# arduino.net
KiCad netlist of a schematic drawn in EAGLE
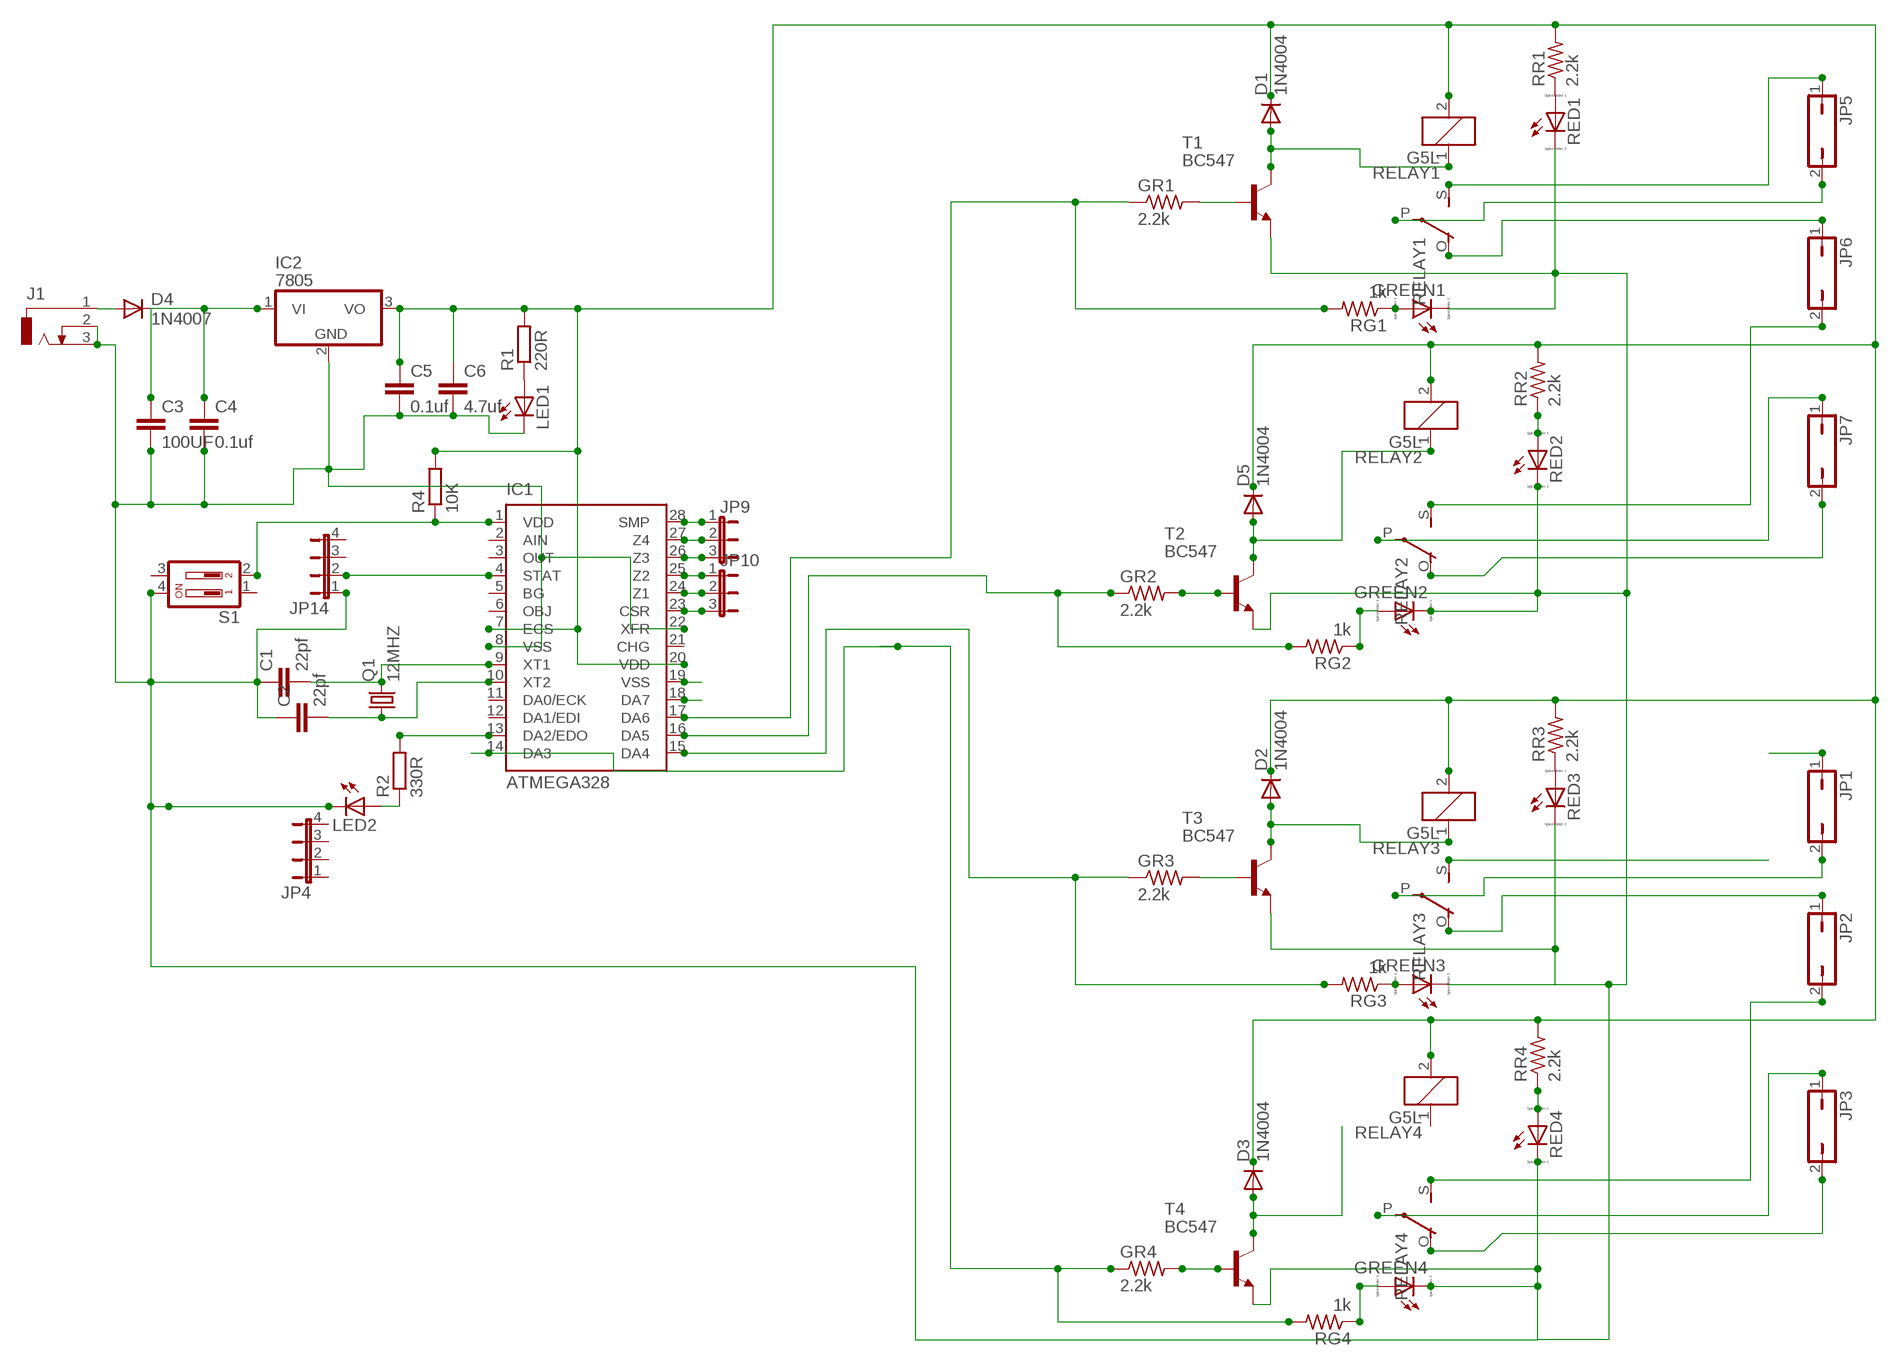
[diagram p0: schematic, sheet 1]

(export (version "E")
  (design (tool "Eeschema 10.0.6"))
  (components
    (comp (ref "C1")
      (value "22pf")
      (footprint "eagle-import:C2.5-2")
      (libsource (lib "eagle-import") (part "C2.5/2"))
    )
    (comp (ref "C2")
      (value "22pf")
      (footprint "eagle-import:C2.5-2")
      (libsource (lib "eagle-import") (part "C2.5/2"))
    )
    (comp (ref "C3")
      (value "100UF")
      (footprint "eagle-import:C2.5-2")
      (libsource (lib "eagle-import") (part "C2.5/2"))
    )
    (comp (ref "C4")
      (value "0.1uf")
      (footprint "eagle-import:C2.5-2")
      (libsource (lib "eagle-import") (part "C2.5/2"))
    )
    (comp (ref "C5")
      (value "0.1uf")
      (footprint "eagle-import:C2.5-2")
      (libsource (lib "eagle-import") (part "C2.5/2"))
    )
    (comp (ref "C6")
      (value "4.7uf")
      (footprint "eagle-import:C2.5-2")
      (libsource (lib "eagle-import") (part "C2.5/2"))
    )
    (comp (ref "D1")
      (value "1N4004")
      (footprint "eagle-import:DO41-10")
      (libsource (lib "eagle-import") (part "1N4004"))
    )
    (comp (ref "D2")
      (value "1N4004")
      (footprint "eagle-import:DO41-10")
      (libsource (lib "eagle-import") (part "1N4004"))
    )
    (comp (ref "D3")
      (value "1N4004")
      (footprint "eagle-import:DO41-10")
      (libsource (lib "eagle-import") (part "1N4004"))
    )
    (comp (ref "D4")
      (value "1N4007")
      (footprint "eagle-import:DO41-10")
      (libsource (lib "eagle-import") (part "1N4004"))
    )
    (comp (ref "D5")
      (value "1N4004")
      (footprint "eagle-import:DO41-10")
      (libsource (lib "eagle-import") (part "1N4004"))
    )
    (comp (ref "GR1")
      (value "2.2k")
      (footprint "eagle-import:0204_7")
      (libsource (lib "eagle-import") (part "R-US_0204/7"))
    )
    (comp (ref "GR2")
      (value "2.2k")
      (footprint "eagle-import:0204_7")
      (libsource (lib "eagle-import") (part "R-US_0204/7"))
    )
    (comp (ref "GR3")
      (value "2.2k")
      (footprint "eagle-import:0204_7")
      (libsource (lib "eagle-import") (part "R-US_0204/7"))
    )
    (comp (ref "GR4")
      (value "2.2k")
      (footprint "eagle-import:0204_7")
      (libsource (lib "eagle-import") (part "R-US_0204/7"))
    )
    (comp (ref "GREEN1")
      (value "LED_ELD260")
      (footprint "eagle-import:LED_LD260")
      (libsource (lib "eagle-import") (part "LED_ELD260"))
    )
    (comp (ref "GREEN2")
      (value "LED_ELD260")
      (footprint "eagle-import:LED_LD260")
      (libsource (lib "eagle-import") (part "LED_ELD260"))
    )
    (comp (ref "GREEN3")
      (value "LED_ELD260")
      (footprint "eagle-import:LED_LD260")
      (libsource (lib "eagle-import") (part "LED_ELD260"))
    )
    (comp (ref "GREEN4")
      (value "LED_ELD260")
      (footprint "eagle-import:LED_LD260")
      (libsource (lib "eagle-import") (part "LED_ELD260"))
    )
    (comp (ref "IC1")
      (value "ATMEGA328")
      (footprint "eagle-import:DIL28-3")
      (libsource (lib "eagle-import") (part "QT9701BD"))
    )
    (comp (ref "IC2")
      (value "7805")
      (footprint "eagle-import:TO220V")
      (libsource (lib "eagle-import") (part "78TV6"))
    )
    (comp (ref "J1")
      (value "DCJ0303")
      (footprint "eagle-import:DCJ0303")
      (libsource (lib "eagle-import") (part "DCJ0303"))
    )
    (comp (ref "JP1")
      (value "JP1Q")
      (footprint "eagle-import:JP1")
      (libsource (lib "eagle-import") (part "JP1Q"))
    )
    (comp (ref "JP2")
      (value "JP1Q")
      (footprint "eagle-import:JP1")
      (libsource (lib "eagle-import") (part "JP1Q"))
    )
    (comp (ref "JP3")
      (value "JP1Q")
      (footprint "eagle-import:JP1")
      (libsource (lib "eagle-import") (part "JP1Q"))
    )
    (comp (ref "JP4")
      (value "JP4E")
      (footprint "eagle-import:JP4")
      (libsource (lib "eagle-import") (part "JP4E"))
    )
    (comp (ref "JP5")
      (value "JP1Q")
      (footprint "eagle-import:JP1")
      (libsource (lib "eagle-import") (part "JP1Q"))
    )
    (comp (ref "JP6")
      (value "JP1Q")
      (footprint "eagle-import:JP1")
      (libsource (lib "eagle-import") (part "JP1Q"))
    )
    (comp (ref "JP7")
      (value "JP1Q")
      (footprint "eagle-import:JP1")
      (libsource (lib "eagle-import") (part "JP1Q"))
    )
    (comp (ref "JP9")
      (value "JP2E")
      (footprint "eagle-import:JP2")
      (libsource (lib "eagle-import") (part "JP2E"))
    )
    (comp (ref "JP10")
      (value "JP2E")
      (footprint "eagle-import:JP2")
      (libsource (lib "eagle-import") (part "JP2E"))
    )
    (comp (ref "JP14")
      (value "JP4E")
      (footprint "eagle-import:JP4")
      (libsource (lib "eagle-import") (part "JP4E"))
    )
    (comp (ref "LED1")
      (value "LED3MM")
      (footprint "eagle-import:LED3MM")
      (libsource (lib "eagle-import") (part "LED3MM"))
    )
    (comp (ref "LED2")
      (value "LED3MM")
      (footprint "eagle-import:LED3MM")
      (libsource (lib "eagle-import") (part "LED3MM"))
    )
    (comp (ref "Q1")
      (value "12MHZ")
      (footprint "eagle-import:HC49_S")
      (libsource (lib "eagle-import") (part "CRYSTALHC49S"))
    )
    (comp (ref "R1")
      (value "220R")
      (footprint "eagle-import:0207_10")
      (libsource (lib "eagle-import") (part "R-EU_0207/10"))
    )
    (comp (ref "R2")
      (value "330R")
      (footprint "eagle-import:0207_10")
      (libsource (lib "eagle-import") (part "R-EU_0207/10"))
    )
    (comp (ref "R4")
      (value "10K")
      (footprint "eagle-import:0207_10")
      (libsource (lib "eagle-import") (part "R-EU_0207/10"))
    )
    (comp (ref "RED1")
      (value "LED_ELD260")
      (footprint "eagle-import:LED_LD260")
      (libsource (lib "eagle-import") (part "LED_ELD260"))
    )
    (comp (ref "RED2")
      (value "LED_ELD260")
      (footprint "eagle-import:LED_LD260")
      (libsource (lib "eagle-import") (part "LED_ELD260"))
    )
    (comp (ref "RED3")
      (value "LED_ELD260")
      (footprint "eagle-import:LED_LD260")
      (libsource (lib "eagle-import") (part "LED_ELD260"))
    )
    (comp (ref "RED4")
      (value "LED_ELD260")
      (footprint "eagle-import:LED_LD260")
      (libsource (lib "eagle-import") (part "LED_ELD260"))
    )
    (comp (ref "RELAY1")
      (value "G5L")
      (footprint "eagle-import:G5LE")
      (libsource (lib "eagle-import") (part "G5L"))
    )
    (comp (ref "RELAY2")
      (value "G5L")
      (footprint "eagle-import:G5LE")
      (libsource (lib "eagle-import") (part "G5L"))
    )
    (comp (ref "RELAY3")
      (value "G5L")
      (footprint "eagle-import:G5LE")
      (libsource (lib "eagle-import") (part "G5L"))
    )
    (comp (ref "RELAY4")
      (value "G5L")
      (footprint "eagle-import:G5LE")
      (libsource (lib "eagle-import") (part "G5L"))
    )
    (comp (ref "RG1")
      (value "1k")
      (footprint "eagle-import:0204_7")
      (libsource (lib "eagle-import") (part "R-US_0204/7"))
    )
    (comp (ref "RG2")
      (value "1k")
      (footprint "eagle-import:0204_7")
      (libsource (lib "eagle-import") (part "R-US_0204/7"))
    )
    (comp (ref "RG3")
      (value "1k")
      (footprint "eagle-import:0204_7")
      (libsource (lib "eagle-import") (part "R-US_0204/7"))
    )
    (comp (ref "RG4")
      (value "1k")
      (footprint "eagle-import:0204_7")
      (libsource (lib "eagle-import") (part "R-US_0204/7"))
    )
    (comp (ref "RR1")
      (value "2.2k")
      (footprint "eagle-import:0204_7")
      (libsource (lib "eagle-import") (part "R-US_0204/7"))
    )
    (comp (ref "RR2")
      (value "2.2k")
      (footprint "eagle-import:0204_7")
      (libsource (lib "eagle-import") (part "R-US_0204/7"))
    )
    (comp (ref "RR3")
      (value "2.2k")
      (footprint "eagle-import:0204_7")
      (libsource (lib "eagle-import") (part "R-US_0204/7"))
    )
    (comp (ref "RR4")
      (value "2.2k")
      (footprint "eagle-import:0204_7")
      (libsource (lib "eagle-import") (part "R-US_0204/7"))
    )
    (comp (ref "S1")
      (value "DP02")
      (footprint "eagle-import:DP-02")
      (fields (field (name "MPN") "MCDP02"))
      (libsource (lib "eagle-import") (part "DP02"))
    )
    (comp (ref "T1")
      (value "BC547")
      (footprint "eagle-import:TO92")
      (libsource (lib "eagle-import") (part "BC547"))
    )
    (comp (ref "T2")
      (value "BC547")
      (footprint "eagle-import:TO92")
      (libsource (lib "eagle-import") (part "BC547"))
    )
    (comp (ref "T3")
      (value "BC547")
      (footprint "eagle-import:TO92")
      (libsource (lib "eagle-import") (part "BC547"))
    )
    (comp (ref "T4")
      (value "BC547")
      (footprint "eagle-import:TO92")
      (libsource (lib "eagle-import") (part "BC547"))
    )
  )
  (nets
    (net (code "1") (name "Net-(D4-PadA)") (class "Default")
      (node (ref "D4") (pin "A") (pinfunction "A_A") (pintype "passive"))
      (node (ref "J1") (pin "1") (pinfunction "1_1") (pintype "passive"))
    )
    (net (code "2") (name "Net-(GREEN1-C)") (class "Default")
      (node (ref "C1") (pin "1") (pinfunction "1_1") (pintype "passive"))
      (node (ref "C2") (pin "1") (pinfunction "1_1") (pintype "passive"))
      (node (ref "C3") (pin "2") (pinfunction "2_2") (pintype "passive"))
      (node (ref "C4") (pin "2") (pinfunction "2_2") (pintype "passive"))
      (node (ref "C5") (pin "2") (pinfunction "2_2") (pintype "passive"))
      (node (ref "C6") (pin "2") (pinfunction "2_2") (pintype "passive"))
      (node (ref "GREEN1") (pin "K") (pinfunction "C_K") (pintype "passive"))
      (node (ref "GREEN2") (pin "K") (pinfunction "C_K") (pintype "passive"))
      (node (ref "GREEN3") (pin "K") (pinfunction "C_K") (pintype "passive"))
      (node (ref "GREEN4") (pin "K") (pinfunction "C_K") (pintype "passive"))
      (node (ref "IC1") (pin "22") (pinfunction "XFR_22") (pintype "output"))
      (node (ref "IC1") (pin "8") (pinfunction "VSS_8") (pintype "input"))
      (node (ref "IC2") (pin "2") (pinfunction "GND_2") (pintype "passive"))
      (node (ref "J1") (pin "2") (pinfunction "2_2") (pintype "passive"))
      (node (ref "J1") (pin "3") (pinfunction "3_3") (pintype "passive"))
      (node (ref "JP14") (pin "1") (pinfunction "1_1") (pintype "passive"))
      (node (ref "LED1") (pin "K") (pinfunction "C_K") (pintype "passive"))
      (node (ref "LED2") (pin "K") (pinfunction "C_K") (pintype "passive"))
      (node (ref "RED1") (pin "K") (pinfunction "C_K") (pintype "passive"))
      (node (ref "RED2") (pin "K") (pinfunction "C_K") (pintype "passive"))
      (node (ref "RED3") (pin "K") (pinfunction "C_K") (pintype "passive"))
      (node (ref "RED4") (pin "K") (pinfunction "C_K") (pintype "passive"))
      (node (ref "S1") (pin "4") (pinfunction "4_4") (pintype "passive"))
      (node (ref "T1") (pin "1") (pinfunction "E_1") (pintype "passive"))
      (node (ref "T2") (pin "1") (pinfunction "E_1") (pintype "passive"))
      (node (ref "T3") (pin "1") (pinfunction "E_1") (pintype "passive"))
      (node (ref "T4") (pin "1") (pinfunction "E_1") (pintype "passive"))
    )
    (net (code "3") (name "Net-(GREEN1-PadA)") (class "Default")
      (node (ref "GREEN1") (pin "A") (pinfunction "A_A") (pintype "passive"))
      (node (ref "RG1") (pin "1") (pinfunction "1_1") (pintype "passive"))
    )
    (net (code "4") (name "Net-(GREEN2-PadA)") (class "Default")
      (node (ref "GREEN2") (pin "A") (pinfunction "A_A") (pintype "passive"))
      (node (ref "RG2") (pin "1") (pinfunction "1_1") (pintype "passive"))
    )
    (net (code "5") (name "Net-(GREEN3-PadA)") (class "Default")
      (node (ref "GREEN3") (pin "A") (pinfunction "A_A") (pintype "passive"))
      (node (ref "RG3") (pin "1") (pinfunction "1_1") (pintype "passive"))
    )
    (net (code "6") (name "Net-(GREEN4-PadA)") (class "Default")
      (node (ref "GREEN4") (pin "A") (pinfunction "A_A") (pintype "passive"))
      (node (ref "RG4") (pin "1") (pinfunction "1_1") (pintype "passive"))
    )
    (net (code "7") (name "Net-(IC1-CSR)") (class "Default")
      (node (ref "IC1") (pin "23") (pinfunction "CSR_23") (pintype "output"))
      (node (ref "JP10") (pin "3") (pinfunction "3_3") (pintype "passive"))
    )
    (net (code "8") (name "Net-(IC1-DA2{slash}EDO)") (class "Default")
      (node (ref "IC1") (pin "13") (pinfunction "DA2/EDO_13") (pintype "output"))
      (node (ref "R2") (pin "2") (pinfunction "2_2") (pintype "passive"))
    )
    (net (code "9") (name "Net-(IC1-DA3)") (class "Default")
      (node (ref "GR4") (pin "1") (pinfunction "1_1") (pintype "passive"))
      (node (ref "IC1") (pin "14") (pinfunction "DA3_14") (pintype "output"))
      (node (ref "RG4") (pin "2") (pinfunction "2_2") (pintype "passive"))
    )
    (net (code "10") (name "Net-(IC1-DA4)") (class "Default")
      (node (ref "GR3") (pin "1") (pinfunction "1_1") (pintype "passive"))
      (node (ref "IC1") (pin "15") (pinfunction "DA4_15") (pintype "output"))
      (node (ref "RG3") (pin "2") (pinfunction "2_2") (pintype "passive"))
    )
    (net (code "11") (name "Net-(IC1-DA5)") (class "Default")
      (node (ref "GR2") (pin "1") (pinfunction "1_1") (pintype "passive"))
      (node (ref "IC1") (pin "16") (pinfunction "DA5_16") (pintype "output"))
      (node (ref "RG2") (pin "2") (pinfunction "2_2") (pintype "passive"))
    )
    (net (code "12") (name "Net-(IC1-DA6)") (class "Default")
      (node (ref "GR1") (pin "1") (pinfunction "1_1") (pintype "passive"))
      (node (ref "IC1") (pin "17") (pinfunction "DA6_17") (pintype "output"))
      (node (ref "RG1") (pin "2") (pinfunction "2_2") (pintype "passive"))
    )
    (net (code "13") (name "Net-(IC1-ECS)") (class "Default")
      (node (ref "C5") (pin "1") (pinfunction "1_1") (pintype "passive"))
      (node (ref "C6") (pin "1") (pinfunction "1_1") (pintype "passive"))
      (node (ref "D1") (pin "C") (pinfunction "C_C") (pintype "passive"))
      (node (ref "D2") (pin "C") (pinfunction "C_C") (pintype "passive"))
      (node (ref "D3") (pin "C") (pinfunction "C_C") (pintype "passive"))
      (node (ref "D5") (pin "C") (pinfunction "C_C") (pintype "passive"))
      (node (ref "IC1") (pin "20") (pinfunction "VDD_20") (pintype "input"))
      (node (ref "IC1") (pin "7") (pinfunction "ECS_7") (pintype "output"))
      (node (ref "IC2") (pin "3") (pinfunction "VO_3") (pintype "passive"))
      (node (ref "R1") (pin "2") (pinfunction "2_2") (pintype "passive"))
      (node (ref "R4") (pin "2") (pinfunction "2_2") (pintype "passive"))
      (node (ref "RELAY1") (pin "2") (pinfunction "2_2") (pintype "passive"))
      (node (ref "RELAY2") (pin "2") (pinfunction "2_2") (pintype "passive"))
      (node (ref "RELAY3") (pin "2") (pinfunction "2_2") (pintype "passive"))
      (node (ref "RELAY4") (pin "2") (pinfunction "2_2") (pintype "passive"))
      (node (ref "RR1") (pin "2") (pinfunction "2_2") (pintype "passive"))
      (node (ref "RR2") (pin "2") (pinfunction "2_2") (pintype "passive"))
      (node (ref "RR3") (pin "2") (pinfunction "2_2") (pintype "passive"))
      (node (ref "RR4") (pin "2") (pinfunction "2_2") (pintype "passive"))
    )
    (net (code "14") (name "Net-(IC1-SMP)") (class "Default")
      (node (ref "IC1") (pin "28") (pinfunction "SMP_28") (pintype "output"))
      (node (ref "JP9") (pin "1") (pinfunction "1_1") (pintype "passive"))
    )
    (net (code "15") (name "Net-(IC1-STAT)") (class "Default")
      (node (ref "IC1") (pin "4") (pinfunction "STAT_4") (pintype "output"))
      (node (ref "JP14") (pin "2") (pinfunction "2_2") (pintype "passive"))
    )
    (net (code "16") (name "Net-(IC1-VDD-Pad1)") (class "Default")
      (node (ref "IC1") (pin "1") (pinfunction "VDD_1") (pintype "input"))
      (node (ref "R4") (pin "1") (pinfunction "1_1") (pintype "passive"))
      (node (ref "S1") (pin "2") (pinfunction "2_2") (pintype "passive"))
    )
    (net (code "17") (name "Net-(IC1-XT1)") (class "Default")
      (node (ref "C1") (pin "2") (pinfunction "2_2") (pintype "passive"))
      (node (ref "IC1") (pin "9") (pinfunction "XT1_9") (pintype "input"))
      (node (ref "Q1") (pin "2") (pinfunction "2_2") (pintype "passive"))
    )
    (net (code "18") (name "Net-(IC1-XT2)") (class "Default")
      (node (ref "C2") (pin "2") (pinfunction "2_2") (pintype "passive"))
      (node (ref "IC1") (pin "10") (pinfunction "XT2_10") (pintype "output"))
      (node (ref "Q1") (pin "1") (pinfunction "1_1") (pintype "passive"))
    )
    (net (code "19") (name "Net-(IC1-Z1)") (class "Default")
      (node (ref "IC1") (pin "24") (pinfunction "Z1_24") (pintype "output"))
      (node (ref "JP10") (pin "2") (pinfunction "2_2") (pintype "passive"))
    )
    (net (code "20") (name "Net-(IC1-Z2)") (class "Default")
      (node (ref "IC1") (pin "25") (pinfunction "Z2_25") (pintype "output"))
      (node (ref "JP10") (pin "1") (pinfunction "1_1") (pintype "passive"))
    )
    (net (code "21") (name "Net-(IC1-Z3)") (class "Default")
      (node (ref "IC1") (pin "26") (pinfunction "Z3_26") (pintype "output"))
      (node (ref "JP9") (pin "3") (pinfunction "3_3") (pintype "passive"))
    )
    (net (code "22") (name "Net-(IC1-Z4)") (class "Default")
      (node (ref "IC1") (pin "27") (pinfunction "Z4_27") (pintype "output"))
      (node (ref "JP9") (pin "2") (pinfunction "2_2") (pintype "passive"))
    )
    (net (code "23") (name "Net-(IC2-VI)") (class "Default")
      (node (ref "C3") (pin "1") (pinfunction "1_1") (pintype "passive"))
      (node (ref "C4") (pin "1") (pinfunction "1_1") (pintype "passive"))
      (node (ref "D4") (pin "C") (pinfunction "C_C") (pintype "passive"))
      (node (ref "IC2") (pin "1") (pinfunction "VI_1") (pintype "input"))
    )
    (net (code "24") (name "Net-(JP1-Pad2)") (class "Default")
      (node (ref "JP1") (pin "2") (pinfunction "2_2") (pintype "passive"))
      (node (ref "RELAY3") (pin "P") (pinfunction "P_P") (pintype "passive"))
    )
    (net (code "25") (name "Net-(JP2-Pad1)") (class "Default")
      (node (ref "JP2") (pin "1") (pinfunction "1_1") (pintype "passive"))
      (node (ref "RELAY3") (pin "O") (pinfunction "O_O") (pintype "passive"))
    )
    (net (code "26") (name "Net-(JP2-Pad2)") (class "Default")
      (node (ref "JP2") (pin "2") (pinfunction "2_2") (pintype "passive"))
      (node (ref "RELAY4") (pin "S") (pinfunction "S_S") (pintype "passive"))
    )
    (net (code "27") (name "Net-(JP3-Pad1)") (class "Default")
      (node (ref "JP3") (pin "1") (pinfunction "1_1") (pintype "passive"))
      (node (ref "RELAY4") (pin "P") (pinfunction "P_P") (pintype "passive"))
    )
    (net (code "28") (name "Net-(JP3-Pad2)") (class "Default")
      (node (ref "JP3") (pin "2") (pinfunction "2_2") (pintype "passive"))
      (node (ref "RELAY4") (pin "O") (pinfunction "O_O") (pintype "passive"))
    )
    (net (code "29") (name "Net-(JP5-Pad1)") (class "Default")
      (node (ref "JP5") (pin "1") (pinfunction "1_1") (pintype "passive"))
      (node (ref "RELAY1") (pin "S") (pinfunction "S_S") (pintype "passive"))
    )
    (net (code "30") (name "Net-(JP5-Pad2)") (class "Default")
      (node (ref "JP5") (pin "2") (pinfunction "2_2") (pintype "passive"))
      (node (ref "RELAY1") (pin "P") (pinfunction "P_P") (pintype "passive"))
    )
    (net (code "31") (name "Net-(JP6-Pad1)") (class "Default")
      (node (ref "JP6") (pin "1") (pinfunction "1_1") (pintype "passive"))
      (node (ref "RELAY1") (pin "O") (pinfunction "O_O") (pintype "passive"))
    )
    (net (code "32") (name "Net-(JP6-Pad2)") (class "Default")
      (node (ref "JP6") (pin "2") (pinfunction "2_2") (pintype "passive"))
      (node (ref "RELAY2") (pin "S") (pinfunction "S_S") (pintype "passive"))
    )
    (net (code "33") (name "Net-(JP7-Pad1)") (class "Default")
      (node (ref "JP7") (pin "1") (pinfunction "1_1") (pintype "passive"))
      (node (ref "RELAY2") (pin "P") (pinfunction "P_P") (pintype "passive"))
    )
    (net (code "34") (name "Net-(JP7-Pad2)") (class "Default")
      (node (ref "JP7") (pin "2") (pinfunction "2_2") (pintype "passive"))
      (node (ref "RELAY2") (pin "O") (pinfunction "O_O") (pintype "passive"))
    )
    (net (code "35") (name "Net-(LED1-PadA)") (class "Default")
      (node (ref "LED1") (pin "A") (pinfunction "A_A") (pintype "passive"))
      (node (ref "R1") (pin "1") (pinfunction "1_1") (pintype "passive"))
    )
    (net (code "36") (name "Net-(LED2-PadA)") (class "Default")
      (node (ref "LED2") (pin "A") (pinfunction "A_A") (pintype "passive"))
      (node (ref "R2") (pin "1") (pinfunction "1_1") (pintype "passive"))
    )
    (net (code "37") (name "Net-(RED1-PadA)") (class "Default")
      (node (ref "RED1") (pin "A") (pinfunction "A_A") (pintype "passive"))
      (node (ref "RR1") (pin "1") (pinfunction "1_1") (pintype "passive"))
    )
    (net (code "38") (name "Net-(RED2-PadA)") (class "Default")
      (node (ref "RED2") (pin "A") (pinfunction "A_A") (pintype "passive"))
      (node (ref "RR2") (pin "1") (pinfunction "1_1") (pintype "passive"))
    )
    (net (code "39") (name "Net-(RED3-PadA)") (class "Default")
      (node (ref "RED3") (pin "A") (pinfunction "A_A") (pintype "passive"))
      (node (ref "RR3") (pin "1") (pinfunction "1_1") (pintype "passive"))
    )
    (net (code "40") (name "Net-(RED4-PadA)") (class "Default")
      (node (ref "RED4") (pin "A") (pinfunction "A_A") (pintype "passive"))
      (node (ref "RR4") (pin "1") (pinfunction "1_1") (pintype "passive"))
    )
    (net (code "41") (name "Net-(T1-B)") (class "Default")
      (node (ref "GR1") (pin "2") (pinfunction "2_2") (pintype "passive"))
      (node (ref "T1") (pin "2") (pinfunction "B_2") (pintype "passive"))
    )
    (net (code "42") (name "Net-(T1-C)") (class "Default")
      (node (ref "D1") (pin "A") (pinfunction "A_A") (pintype "passive"))
      (node (ref "RELAY1") (pin "1") (pinfunction "1_1") (pintype "passive"))
      (node (ref "T1") (pin "3") (pinfunction "C_3") (pintype "passive"))
    )
    (net (code "43") (name "Net-(T2-B)") (class "Default")
      (node (ref "GR2") (pin "2") (pinfunction "2_2") (pintype "passive"))
      (node (ref "T2") (pin "2") (pinfunction "B_2") (pintype "passive"))
    )
    (net (code "44") (name "Net-(T2-C)") (class "Default")
      (node (ref "D5") (pin "A") (pinfunction "A_A") (pintype "passive"))
      (node (ref "RELAY2") (pin "1") (pinfunction "1_1") (pintype "passive"))
      (node (ref "T2") (pin "3") (pinfunction "C_3") (pintype "passive"))
    )
    (net (code "45") (name "Net-(T3-B)") (class "Default")
      (node (ref "GR3") (pin "2") (pinfunction "2_2") (pintype "passive"))
      (node (ref "T3") (pin "2") (pinfunction "B_2") (pintype "passive"))
    )
    (net (code "46") (name "Net-(T3-C)") (class "Default")
      (node (ref "D2") (pin "A") (pinfunction "A_A") (pintype "passive"))
      (node (ref "RELAY3") (pin "1") (pinfunction "1_1") (pintype "passive"))
      (node (ref "T3") (pin "3") (pinfunction "C_3") (pintype "passive"))
    )
    (net (code "47") (name "Net-(T4-B)") (class "Default")
      (node (ref "GR4") (pin "2") (pinfunction "2_2") (pintype "passive"))
      (node (ref "T4") (pin "2") (pinfunction "B_2") (pintype "passive"))
    )
    (net (code "48") (name "Net-(T4-C)") (class "Default")
      (node (ref "D3") (pin "A") (pinfunction "A_A") (pintype "passive"))
      (node (ref "T4") (pin "3") (pinfunction "C_3") (pintype "passive"))
    )
    (net (code "49") (name "unconnected-(IC1-AIN-Pad2)") (class "Default")
      (node (ref "IC1") (pin "2") (pinfunction "AIN_2") (pintype "input"))
    )
    (net (code "50") (name "unconnected-(IC1-BG-Pad5)") (class "Default")
      (node (ref "IC1") (pin "5") (pinfunction "BG_5") (pintype "input"))
    )
    (net (code "51") (name "unconnected-(IC1-CHG-Pad21)") (class "Default")
      (node (ref "IC1") (pin "21") (pinfunction "CHG_21") (pintype "output"))
    )
    (net (code "52") (name "unconnected-(IC1-DA0{slash}ECK-Pad11)") (class "Default")
      (node (ref "IC1") (pin "11") (pinfunction "DA0/ECK_11") (pintype "output"))
    )
    (net (code "53") (name "unconnected-(IC1-DA1{slash}EDI-Pad12)") (class "Default")
      (node (ref "IC1") (pin "12") (pinfunction "DA1/EDI_12") (pintype "output"))
    )
    (net (code "54") (name "unconnected-(IC1-DA7-Pad18)") (class "Default")
      (node (ref "IC1") (pin "18") (pinfunction "DA7_18") (pintype "output"))
    )
    (net (code "55") (name "unconnected-(IC1-OBJ-Pad6)") (class "Default")
      (node (ref "IC1") (pin "6") (pinfunction "OBJ_6") (pintype "input"))
    )
    (net (code "56") (name "unconnected-(IC1-OUT-Pad3)") (class "Default")
      (node (ref "IC1") (pin "3") (pinfunction "OUT_3") (pintype "output"))
    )
    (net (code "57") (name "unconnected-(IC1-VSS-Pad19)") (class "Default")
      (node (ref "IC1") (pin "19") (pinfunction "VSS_19") (pintype "input"))
    )
    (net (code "58") (name "unconnected-(JP1-Pad1)") (class "Default")
      (node (ref "JP1") (pin "1") (pinfunction "1_1") (pintype "passive"))
    )
    (net (code "59") (name "unconnected-(JP4-Pad1)") (class "Default")
      (node (ref "JP4") (pin "1") (pinfunction "1_1") (pintype "passive"))
    )
    (net (code "60") (name "unconnected-(JP4-Pad2)") (class "Default")
      (node (ref "JP4") (pin "2") (pinfunction "2_2") (pintype "passive"))
    )
    (net (code "61") (name "unconnected-(JP4-Pad3)") (class "Default")
      (node (ref "JP4") (pin "3") (pinfunction "3_3") (pintype "passive"))
    )
    (net (code "62") (name "unconnected-(JP4-Pad4)") (class "Default")
      (node (ref "JP4") (pin "4") (pinfunction "4_4") (pintype "passive"))
    )
    (net (code "63") (name "unconnected-(JP14-Pad3)") (class "Default")
      (node (ref "JP14") (pin "3") (pinfunction "3_3") (pintype "passive"))
    )
    (net (code "64") (name "unconnected-(JP14-Pad4)") (class "Default")
      (node (ref "JP14") (pin "4") (pinfunction "4_4") (pintype "passive"))
    )
    (net (code "65") (name "unconnected-(RELAY3-PadS)") (class "Default")
      (node (ref "RELAY3") (pin "S") (pinfunction "S_S") (pintype "passive"))
    )
    (net (code "66") (name "unconnected-(RELAY4-Pad1)") (class "Default")
      (node (ref "RELAY4") (pin "1") (pinfunction "1_1") (pintype "passive"))
    )
    (net (code "67") (name "unconnected-(S1-Pad1)") (class "Default")
      (node (ref "S1") (pin "1") (pinfunction "1_1") (pintype "passive"))
    )
    (net (code "68") (name "unconnected-(S1-Pad3)") (class "Default")
      (node (ref "S1") (pin "3") (pinfunction "3_3") (pintype "passive"))
    )
  )
)
